# DIY_DAP_PCB_Power.net
KiCad netlist of a schematic drawn in Altium Designer
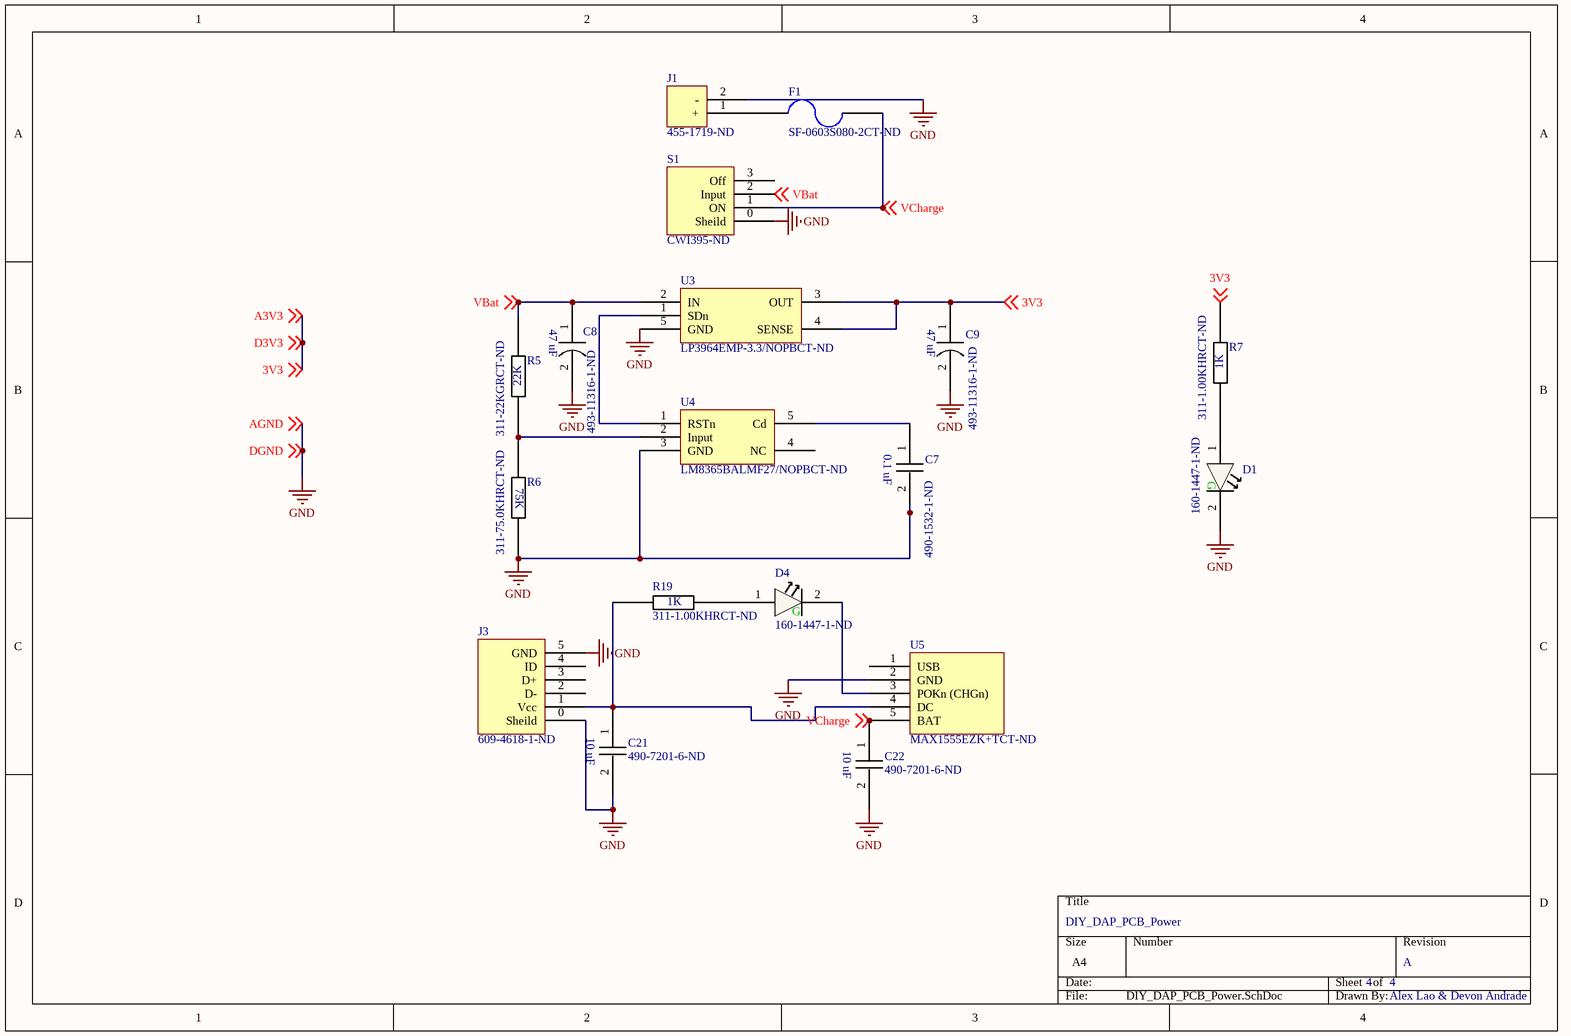
[diagram p0: DIY_DAP_PCB_Power.SchDoc]

(export (version "E")
  (design (tool "Eeschema 10.0.6"))
  (components
    (comp (ref "C7")
      (value "490-1532-1-ND")
      (footprint "0603")
      (description "0603 0.1 uF - 16V - Ceramic Capacitor")
      (libsource (lib "DIY_DAP_PCB_Library") (part "490-1532-1-ND"))
    )
    (comp (ref "C8")
      (value "493-11316-1-ND")
      (footprint "493-11316-1-ND")
      (description "47 uF - 10V - Electrolytic Capacitor")
      (libsource (lib "DIY_DAP_PCB_Library") (part "493-11316-1-ND"))
    )
    (comp (ref "C9")
      (value "493-11316-1-ND")
      (footprint "493-11316-1-ND")
      (description "47 uF - 10V - Electrolytic Capacitor")
      (libsource (lib "DIY_DAP_PCB_Library") (part "493-11316-1-ND"))
    )
    (comp (ref "C21")
      (value "490-7201-6-ND")
      (footprint "0603")
      (description "0603 10 uF - 16V - Ceramic Capacitor")
      (libsource (lib "DIY_DAP_PCB_Library") (part "490-7201-6-ND"))
    )
    (comp (ref "C22")
      (value "490-7201-6-ND")
      (footprint "0603")
      (description "0603 10 uF - 16V - Ceramic Capacitor")
      (libsource (lib "DIY_DAP_PCB_Library") (part "490-7201-6-ND"))
    )
    (comp (ref "D1")
      (value "160-1447-1-ND")
      (footprint "0603")
      (description "Green LED (0603)")
      (libsource (lib "DIY_DAP_PCB_Library") (part "160-1447-1-ND"))
    )
    (comp (ref "D4")
      (value "160-1447-1-ND")
      (footprint "0603")
      (description "Green LED (0603)")
      (libsource (lib "DIY_DAP_PCB_Library") (part "160-1447-1-ND"))
    )
    (comp (ref "F1")
      (value "SF-0603S080-2CT-ND")
      (footprint "0603")
      (description "800 mA 32VDC Fuse")
      (libsource (lib "DIY_DAP_PCB_Library") (part "SF-0603S080-2CT-ND"))
    )
    (comp (ref "J1")
      (value "455-1719-ND")
      (footprint "455-1719-ND")
      (description "JST-PH Battery Connector")
      (libsource (lib "DIY_DAP_PCB_Library") (part "455-1719-ND"))
    )
    (comp (ref "J3")
      (value "609-4618-1-ND")
      (footprint "609-4618-1-ND")
      (description "USB Micro-B")
      (libsource (lib "DIY_DAP_PCB_Library") (part "609-4618-1-ND"))
    )
    (comp (ref "R5")
      (value "311-22KGRCT-ND")
      (footprint "0603")
      (description "22k Ohm Resistor")
      (libsource (lib "DIY_DAP_PCB_Library") (part "311-22KGRCT-ND"))
    )
    (comp (ref "R6")
      (value "311-75.0KHRCT-ND")
      (footprint "0603")
      (description "75k Ohm Resistor")
      (libsource (lib "DIY_DAP_PCB_Library") (part "311-75.0KHRCT-ND"))
    )
    (comp (ref "R7")
      (value "311-1.00KHRCT-ND")
      (footprint "0603")
      (description "1k Ohm Resistor")
      (libsource (lib "DIY_DAP_PCB_Library") (part "311-1.00KHRCT-ND"))
    )
    (comp (ref "R19")
      (value "311-1.00KHRCT-ND")
      (footprint "0603")
      (description "1k Ohm Resistor")
      (libsource (lib "DIY_DAP_PCB_Library") (part "311-1.00KHRCT-ND"))
    )
    (comp (ref "S1")
      (value "CWI395-ND")
      (footprint "CWI395-ND")
      (libsource (lib "DIY_DAP_PCB_Library") (part "CWI395-ND"))
    )
    (comp (ref "U3")
      (value "LP3964EMP-3.3/NOPBCT-ND")
      (footprint "LP3964EMP-3.3/NOPBCT-ND")
      (description "3.3V LDO")
      (libsource (lib "DIY_DAP_PCB_Library") (part "LP3964EMP-3.3/NOPBCT-ND"))
    )
    (comp (ref "U4")
      (value "LM8365BALMF27/NOPBCT-ND")
      (footprint "LM8365BALMF27/NOPBCT-ND")
      (description "Undervoltage Reset Controller")
      (libsource (lib "DIY_DAP_PCB_Library") (part "LM8365BALMF27/NOPBCT-ND"))
    )
    (comp (ref "U5")
      (value "MAX1555EZK+TCT-ND")
      (footprint "MAX1555EZK+TCT-ND")
      (description "LiPo Charger")
      (libsource (lib "DIY_DAP_PCB_Library") (part "MAX1555EZK+TCT-ND"))
    )
  )
  (nets
    (net (code "1") (name "3V3") (class "Default")
      (node (ref "C9") (pin "1") (pinfunction "1_1") (pintype "passive"))
      (node (ref "R7") (pin "2") (pinfunction "2_2") (pintype "passive"))
      (node (ref "U3") (pin "3") (pinfunction "OUT_3") (pintype "passive"))
      (node (ref "U3") (pin "4") (pinfunction "SENSE_4") (pintype "passive"))
    )
    (net (code "2") (name "AGND") (class "Default")
      (node (ref "C21") (pin "2") (pinfunction "2_2") (pintype "passive"))
      (node (ref "C22") (pin "2") (pinfunction "2_2") (pintype "passive"))
      (node (ref "C7") (pin "2") (pinfunction "2_2") (pintype "passive"))
      (node (ref "C8") (pin "2") (pinfunction "2_2") (pintype "passive"))
      (node (ref "C9") (pin "2") (pinfunction "2_2") (pintype "passive"))
      (node (ref "D1") (pin "2") (pinfunction "-_2") (pintype "passive"))
      (node (ref "J1") (pin "2") (pinfunction "-_2") (pintype "passive"))
      (node (ref "J3") (pin "0") (pinfunction "Sheild_0") (pintype "passive"))
      (node (ref "J3") (pin "5") (pinfunction "GND_5") (pintype "passive"))
      (node (ref "R6") (pin "2") (pinfunction "2_2") (pintype "passive"))
      (node (ref "S1") (pin "0") (pinfunction "Sheild_0") (pintype "passive"))
      (node (ref "U3") (pin "5") (pinfunction "GND_5") (pintype "passive"))
      (node (ref "U4") (pin "3") (pinfunction "GND_3") (pintype "passive"))
      (node (ref "U5") (pin "2") (pinfunction "GND_2") (pintype "passive"))
    )
    (net (code "3") (name "Net-(D1-+)") (class "Default")
      (node (ref "D1") (pin "1") (pinfunction "+_1") (pintype "passive"))
      (node (ref "R7") (pin "1") (pinfunction "1_1") (pintype "passive"))
    )
    (net (code "4") (name "Net-(D4-+)") (class "Default")
      (node (ref "D4") (pin "1") (pinfunction "+_1") (pintype "passive"))
      (node (ref "R19") (pin "2") (pinfunction "2_2") (pintype "passive"))
    )
    (net (code "5") (name "Net-(D4--)") (class "Default")
      (node (ref "D4") (pin "2") (pinfunction "-_2") (pintype "passive"))
      (node (ref "U5") (pin "3") (pinfunction "POKn_(CHGn)_3") (pintype "passive"))
    )
    (net (code "6") (name "Net-(J1-+)") (class "Default")
      (node (ref "F1") (pin "1") (pinfunction "1_1") (pintype "passive"))
      (node (ref "J1") (pin "1") (pinfunction "+_1") (pintype "passive"))
    )
    (net (code "7") (name "Net-(J3-Vcc)") (class "Default")
      (node (ref "C21") (pin "1") (pinfunction "1_1") (pintype "passive"))
      (node (ref "J3") (pin "1") (pinfunction "Vcc_1") (pintype "passive"))
      (node (ref "R19") (pin "1") (pinfunction "1_1") (pintype "passive"))
      (node (ref "U5") (pin "4") (pinfunction "DC_4") (pintype "passive"))
    )
    (net (code "8") (name "Net-(U3-SDn)") (class "Default")
      (node (ref "U3") (pin "1") (pinfunction "SDn_1") (pintype "passive"))
      (node (ref "U4") (pin "1") (pinfunction "RSTn_1") (pintype "passive"))
    )
    (net (code "9") (name "Net-(U4-Cd)") (class "Default")
      (node (ref "C7") (pin "1") (pinfunction "1_1") (pintype "passive"))
      (node (ref "U4") (pin "5") (pinfunction "Cd_5") (pintype "passive"))
    )
    (net (code "10") (name "Net-(U4-Input)") (class "Default")
      (node (ref "R5") (pin "1") (pinfunction "1_1") (pintype "passive"))
      (node (ref "R6") (pin "1") (pinfunction "1_1") (pintype "passive"))
      (node (ref "U4") (pin "2") (pinfunction "Input_2") (pintype "passive"))
    )
    (net (code "11") (name "VBat") (class "Default")
      (node (ref "C8") (pin "1") (pinfunction "1_1") (pintype "passive"))
      (node (ref "R5") (pin "2") (pinfunction "2_2") (pintype "passive"))
      (node (ref "S1") (pin "2") (pinfunction "Input_2") (pintype "passive"))
      (node (ref "U3") (pin "2") (pinfunction "IN_2") (pintype "passive"))
    )
    (net (code "12") (name "VCharge") (class "Default")
      (node (ref "C22") (pin "1") (pinfunction "1_1") (pintype "passive"))
      (node (ref "F1") (pin "2") (pinfunction "2_2") (pintype "passive"))
      (node (ref "S1") (pin "1") (pinfunction "ON_1") (pintype "passive"))
      (node (ref "U5") (pin "5") (pinfunction "BAT_5") (pintype "passive"))
    )
    (net (code "13") (name "unconnected-(J3-D+-Pad3)") (class "Default")
      (node (ref "J3") (pin "3") (pinfunction "D+_3") (pintype "passive"))
    )
    (net (code "14") (name "unconnected-(J3-D--Pad2)") (class "Default")
      (node (ref "J3") (pin "2") (pinfunction "D-_2") (pintype "passive"))
    )
    (net (code "15") (name "unconnected-(J3-ID-Pad4)") (class "Default")
      (node (ref "J3") (pin "4") (pinfunction "ID_4") (pintype "passive"))
    )
    (net (code "16") (name "unconnected-(S1-Off-Pad3)") (class "Default")
      (node (ref "S1") (pin "3") (pinfunction "Off_3") (pintype "passive"))
    )
    (net (code "17") (name "unconnected-(U4-NC-Pad4)") (class "Default")
      (node (ref "U4") (pin "4") (pinfunction "NC_4") (pintype "passive"))
    )
    (net (code "18") (name "unconnected-(U5-USB-Pad1)") (class "Default")
      (node (ref "U5") (pin "1") (pinfunction "USB_1") (pintype "passive"))
    )
  )
)
